# drivepod_dsub.net
KiCad netlist of a schematic drawn in EAGLE
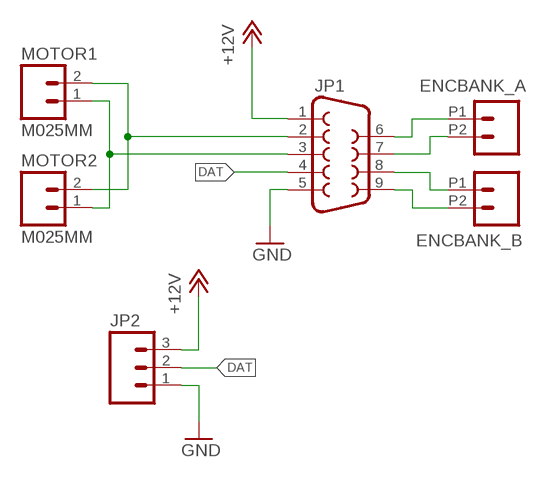
[diagram p0: schematic, sheet 1]

(export (version "E")
  (design (tool "Eeschema 10.0.6"))
  (components
    (comp (ref "ENCBANK_A")
      (value "M022.54MM_SCREWTERM")
      (footprint "eagle-import:1X02_2.54_SCREWTERM")
      (libsource (lib "eagle-import") (part "M022.54MM_SCREWTERM"))
    )
    (comp (ref "ENCBANK_B")
      (value "M022.54MM_SCREWTERM")
      (footprint "eagle-import:1X02_2.54_SCREWTERM")
      (libsource (lib "eagle-import") (part "M022.54MM_SCREWTERM"))
    )
    (comp (ref "JP1")
      (value "DB9MALE")
      (footprint "eagle-import:DB9_MALE")
      (libsource (lib "eagle-import") (part "DB9MALE"))
    )
    (comp (ref "JP2")
      (value "M03SCREW")
      (footprint "eagle-import:SCREWTERMINAL-3.5MM-3")
      (libsource (lib "eagle-import") (part "M03SCREW"))
    )
    (comp (ref "MOTOR1")
      (value "M025MM")
      (footprint "eagle-import:SCREWTERMINAL-5MM-2")
      (libsource (lib "eagle-import") (part "M025MM"))
    )
    (comp (ref "MOTOR2")
      (value "M025MM")
      (footprint "eagle-import:SCREWTERMINAL-5MM-2")
      (libsource (lib "eagle-import") (part "M025MM"))
    )
  )
  (nets
    (net (code "1") (name "+12V") (class "Default")
      (node (ref "JP1") (pin "1") (pinfunction "1_1") (pintype "passive"))
      (node (ref "JP2") (pin "3") (pinfunction "3_3") (pintype "passive"))
    )
    (net (code "2") (name "DAT") (class "Default")
      (node (ref "JP1") (pin "4") (pinfunction "4_4") (pintype "passive"))
      (node (ref "JP2") (pin "2") (pinfunction "2_2") (pintype "passive"))
    )
    (net (code "3") (name "GND") (class "Default")
      (node (ref "JP1") (pin "5") (pinfunction "5_5") (pintype "passive"))
      (node (ref "JP2") (pin "1") (pinfunction "1_1") (pintype "passive"))
    )
    (net (code "4") (name "Net-(ENCBANK_A-1)") (class "Default")
      (node (ref "ENCBANK_A") (pin "P1") (pinfunction "1_P1") (pintype "passive"))
      (node (ref "JP1") (pin "6") (pinfunction "6_6") (pintype "passive"))
    )
    (net (code "5") (name "Net-(ENCBANK_A-2)") (class "Default")
      (node (ref "ENCBANK_A") (pin "P2") (pinfunction "2_P2") (pintype "passive"))
      (node (ref "JP1") (pin "7") (pinfunction "7_7") (pintype "passive"))
    )
    (net (code "6") (name "Net-(ENCBANK_B-1)") (class "Default")
      (node (ref "ENCBANK_B") (pin "P1") (pinfunction "1_P1") (pintype "passive"))
      (node (ref "JP1") (pin "8") (pinfunction "8_8") (pintype "passive"))
    )
    (net (code "7") (name "Net-(ENCBANK_B-2)") (class "Default")
      (node (ref "ENCBANK_B") (pin "P2") (pinfunction "2_P2") (pintype "passive"))
      (node (ref "JP1") (pin "9") (pinfunction "9_9") (pintype "passive"))
    )
    (net (code "8") (name "Net-(JP1-Pad2)") (class "Default")
      (node (ref "JP1") (pin "2") (pinfunction "2_2") (pintype "passive"))
      (node (ref "MOTOR1") (pin "2") (pinfunction "2_2") (pintype "passive"))
      (node (ref "MOTOR2") (pin "2") (pinfunction "2_2") (pintype "passive"))
    )
    (net (code "9") (name "Net-(JP1-Pad3)") (class "Default")
      (node (ref "JP1") (pin "3") (pinfunction "3_3") (pintype "passive"))
      (node (ref "MOTOR1") (pin "1") (pinfunction "1_1") (pintype "passive"))
      (node (ref "MOTOR2") (pin "1") (pinfunction "1_1") (pintype "passive"))
    )
  )
)
